# marquee_h.net
KiCad netlist of a schematic drawn in EAGLE
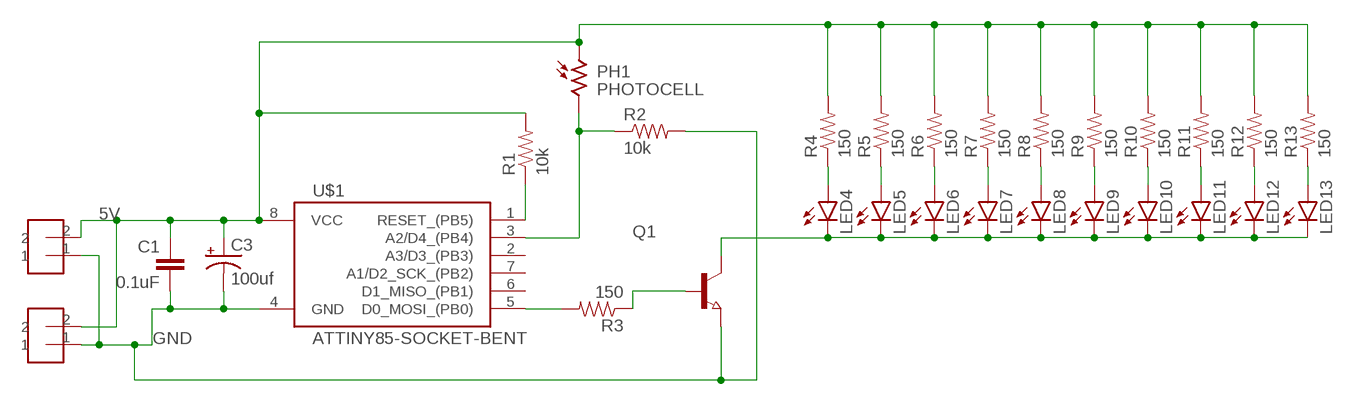
[diagram p0: schematic, sheet 1]

(export (version "E")
  (design (tool "Eeschema 10.0.6"))
  (components
    (comp (ref "C1")
      (value "0.1uF")
      (footprint "eagle-import:0805")
      (libsource (lib "eagle-import") (part "CAP-0805"))
    )
    (comp (ref "C3")
      (value "100uf")
      (footprint "eagle-import:PANASONIC_D")
      (libsource (lib "eagle-import") (part "CAP_POLD"))
    )
    (comp (ref "LED4")
      (value "LED0603")
      (footprint "eagle-import:LED-0603")
      (libsource (lib "eagle-import") (part "LED0603"))
    )
    (comp (ref "LED5")
      (value "LED0603")
      (footprint "eagle-import:LED-0603")
      (libsource (lib "eagle-import") (part "LED0603"))
    )
    (comp (ref "LED6")
      (value "LED0603")
      (footprint "eagle-import:LED-0603")
      (libsource (lib "eagle-import") (part "LED0603"))
    )
    (comp (ref "LED7")
      (value "LED0603")
      (footprint "eagle-import:LED-0603")
      (libsource (lib "eagle-import") (part "LED0603"))
    )
    (comp (ref "LED8")
      (value "LED0603")
      (footprint "eagle-import:LED-0603")
      (libsource (lib "eagle-import") (part "LED0603"))
    )
    (comp (ref "LED9")
      (value "LED0603")
      (footprint "eagle-import:LED-0603")
      (libsource (lib "eagle-import") (part "LED0603"))
    )
    (comp (ref "LED10")
      (value "LED0603")
      (footprint "eagle-import:LED-0603")
      (libsource (lib "eagle-import") (part "LED0603"))
    )
    (comp (ref "LED11")
      (value "LED0603")
      (footprint "eagle-import:LED-0603")
      (libsource (lib "eagle-import") (part "LED0603"))
    )
    (comp (ref "LED12")
      (value "LED0603")
      (footprint "eagle-import:LED-0603")
      (libsource (lib "eagle-import") (part "LED0603"))
    )
    (comp (ref "LED13")
      (value "LED0603")
      (footprint "eagle-import:LED-0603")
      (libsource (lib "eagle-import") (part "LED0603"))
    )
    (comp (ref "PH1")
      (value "PHOTOCELL")
      (footprint "eagle-import:PHOTOCELL_ADAFRUIT")
      (libsource (lib "eagle-import") (part "PHOTOCELL"))
    )
    (comp (ref "Q1")
      (value "TRANSISTOR-NPN-SOT23")
      (footprint "eagle-import:SOT23")
      (libsource (lib "eagle-import") (part "TRANSISTOR-NPN-SOT23"))
    )
    (comp (ref "R1")
      (value "10k")
      (footprint "eagle-import:0805")
      (libsource (lib "eagle-import") (part "RESISTOR-0805"))
    )
    (comp (ref "R2")
      (value "10k")
      (footprint "eagle-import:0805")
      (libsource (lib "eagle-import") (part "RESISTOR-0805"))
    )
    (comp (ref "R3")
      (value "150")
      (footprint "eagle-import:0805")
      (libsource (lib "eagle-import") (part "RESISTOR-0805"))
    )
    (comp (ref "R4")
      (value "150")
      (footprint "eagle-import:0603-RES")
      (libsource (lib "eagle-import") (part "RESISTOR0603"))
    )
    (comp (ref "R5")
      (value "150")
      (footprint "eagle-import:0603-RES")
      (libsource (lib "eagle-import") (part "RESISTOR0603"))
    )
    (comp (ref "R6")
      (value "150")
      (footprint "eagle-import:0603-RES")
      (libsource (lib "eagle-import") (part "RESISTOR0603"))
    )
    (comp (ref "R7")
      (value "150")
      (footprint "eagle-import:0603-RES")
      (libsource (lib "eagle-import") (part "RESISTOR0603"))
    )
    (comp (ref "R8")
      (value "150")
      (footprint "eagle-import:0603-RES")
      (libsource (lib "eagle-import") (part "RESISTOR0603"))
    )
    (comp (ref "R9")
      (value "150")
      (footprint "eagle-import:0603-RES")
      (libsource (lib "eagle-import") (part "RESISTOR0603"))
    )
    (comp (ref "R10")
      (value "150")
      (footprint "eagle-import:0603-RES")
      (libsource (lib "eagle-import") (part "RESISTOR0603"))
    )
    (comp (ref "R11")
      (value "150")
      (footprint "eagle-import:0603-RES")
      (libsource (lib "eagle-import") (part "RESISTOR0603"))
    )
    (comp (ref "R12")
      (value "150")
      (footprint "eagle-import:0603-RES")
      (libsource (lib "eagle-import") (part "RESISTOR0603"))
    )
    (comp (ref "R13")
      (value "150")
      (footprint "eagle-import:0603-RES")
      (libsource (lib "eagle-import") (part "RESISTOR0603"))
    )
    (comp (ref "U$1")
      (value "ATTINY85-SOCKET-BENT")
      (footprint "eagle-import:SOCKET-8PIN-BENT")
      (libsource (lib "eagle-import") (part "ATTINY85-SOCKET-BENT"))
    )
    (comp (ref "U$2")
      (value "HEADER-2")
      (footprint "eagle-import:HEADER-2")
      (libsource (lib "eagle-import") (part "HEADER-2"))
    )
    (comp (ref "U$3")
      (value "HEADER-2")
      (footprint "eagle-import:HEADER-2")
      (libsource (lib "eagle-import") (part "HEADER-2"))
    )
  )
  (nets
    (net (code "1") (name "/5V") (class "Default")
      (node (ref "C1") (pin "1") (pinfunction "1_1") (pintype "passive"))
      (node (ref "C3") (pin "+") (pinfunction "+_+") (pintype "passive"))
      (node (ref "PH1") (pin "1") (pinfunction "1_1") (pintype "passive"))
      (node (ref "R1") (pin "2") (pinfunction "2_2") (pintype "passive"))
      (node (ref "R10") (pin "2") (pinfunction "2_2") (pintype "passive"))
      (node (ref "R11") (pin "2") (pinfunction "2_2") (pintype "passive"))
      (node (ref "R12") (pin "2") (pinfunction "2_2") (pintype "passive"))
      (node (ref "R13") (pin "2") (pinfunction "2_2") (pintype "passive"))
      (node (ref "R4") (pin "2") (pinfunction "2_2") (pintype "passive"))
      (node (ref "R5") (pin "2") (pinfunction "2_2") (pintype "passive"))
      (node (ref "R6") (pin "2") (pinfunction "2_2") (pintype "passive"))
      (node (ref "R7") (pin "2") (pinfunction "2_2") (pintype "passive"))
      (node (ref "R8") (pin "2") (pinfunction "2_2") (pintype "passive"))
      (node (ref "R9") (pin "2") (pinfunction "2_2") (pintype "passive"))
      (node (ref "U$1") (pin "8") (pinfunction "VCC_8") (pintype "power_in"))
      (node (ref "U$2") (pin "2") (pinfunction "2_2") (pintype "bidirectional"))
      (node (ref "U$3") (pin "2") (pinfunction "2_2") (pintype "bidirectional"))
    )
    (net (code "2") (name "/GND") (class "Default")
      (node (ref "C1") (pin "2") (pinfunction "2_2") (pintype "passive"))
      (node (ref "C3") (pin "-") (pinfunction "-_-") (pintype "passive"))
      (node (ref "Q1") (pin "2") (pinfunction "E_2") (pintype "passive"))
      (node (ref "R2") (pin "2") (pinfunction "2_2") (pintype "passive"))
      (node (ref "U$1") (pin "4") (pinfunction "GND_4") (pintype "power_in"))
      (node (ref "U$2") (pin "1") (pinfunction "1_1") (pintype "bidirectional"))
      (node (ref "U$3") (pin "1") (pinfunction "1_1") (pintype "bidirectional"))
    )
    (net (code "3") (name "Net-(LED4-PadA)") (class "Default")
      (node (ref "LED4") (pin "A") (pinfunction "A_A") (pintype "passive"))
      (node (ref "R4") (pin "1") (pinfunction "1_1") (pintype "passive"))
    )
    (net (code "4") (name "Net-(LED5-PadA)") (class "Default")
      (node (ref "LED5") (pin "A") (pinfunction "A_A") (pintype "passive"))
      (node (ref "R5") (pin "1") (pinfunction "1_1") (pintype "passive"))
    )
    (net (code "5") (name "Net-(LED6-PadA)") (class "Default")
      (node (ref "LED6") (pin "A") (pinfunction "A_A") (pintype "passive"))
      (node (ref "R6") (pin "1") (pinfunction "1_1") (pintype "passive"))
    )
    (net (code "6") (name "Net-(LED7-PadA)") (class "Default")
      (node (ref "LED7") (pin "A") (pinfunction "A_A") (pintype "passive"))
      (node (ref "R7") (pin "1") (pinfunction "1_1") (pintype "passive"))
    )
    (net (code "7") (name "Net-(LED8-PadA)") (class "Default")
      (node (ref "LED8") (pin "A") (pinfunction "A_A") (pintype "passive"))
      (node (ref "R8") (pin "1") (pinfunction "1_1") (pintype "passive"))
    )
    (net (code "8") (name "Net-(LED9-PadA)") (class "Default")
      (node (ref "LED9") (pin "A") (pinfunction "A_A") (pintype "passive"))
      (node (ref "R9") (pin "1") (pinfunction "1_1") (pintype "passive"))
    )
    (net (code "9") (name "Net-(LED10-PadA)") (class "Default")
      (node (ref "LED10") (pin "A") (pinfunction "A_A") (pintype "passive"))
      (node (ref "R10") (pin "1") (pinfunction "1_1") (pintype "passive"))
    )
    (net (code "10") (name "Net-(LED11-PadA)") (class "Default")
      (node (ref "LED11") (pin "A") (pinfunction "A_A") (pintype "passive"))
      (node (ref "R11") (pin "1") (pinfunction "1_1") (pintype "passive"))
    )
    (net (code "11") (name "Net-(LED12-PadA)") (class "Default")
      (node (ref "LED12") (pin "A") (pinfunction "A_A") (pintype "passive"))
      (node (ref "R12") (pin "1") (pinfunction "1_1") (pintype "passive"))
    )
    (net (code "12") (name "Net-(LED13-PadA)") (class "Default")
      (node (ref "LED13") (pin "A") (pinfunction "A_A") (pintype "passive"))
      (node (ref "R13") (pin "1") (pinfunction "1_1") (pintype "passive"))
    )
    (net (code "13") (name "Net-(Q1-B)") (class "Default")
      (node (ref "Q1") (pin "1") (pinfunction "B_1") (pintype "passive"))
      (node (ref "R3") (pin "1") (pinfunction "1_1") (pintype "passive"))
    )
    (net (code "14") (name "Net-(Q1-C)") (class "Default")
      (node (ref "LED10") (pin "C") (pinfunction "C_C") (pintype "passive"))
      (node (ref "LED11") (pin "C") (pinfunction "C_C") (pintype "passive"))
      (node (ref "LED12") (pin "C") (pinfunction "C_C") (pintype "passive"))
      (node (ref "LED13") (pin "C") (pinfunction "C_C") (pintype "passive"))
      (node (ref "LED4") (pin "C") (pinfunction "C_C") (pintype "passive"))
      (node (ref "LED5") (pin "C") (pinfunction "C_C") (pintype "passive"))
      (node (ref "LED6") (pin "C") (pinfunction "C_C") (pintype "passive"))
      (node (ref "LED7") (pin "C") (pinfunction "C_C") (pintype "passive"))
      (node (ref "LED8") (pin "C") (pinfunction "C_C") (pintype "passive"))
      (node (ref "LED9") (pin "C") (pinfunction "C_C") (pintype "passive"))
      (node (ref "Q1") (pin "3") (pinfunction "C_3") (pintype "passive"))
    )
    (net (code "15") (name "Net-(U$1-A2{slash}D4_(PB4))") (class "Default")
      (node (ref "PH1") (pin "2") (pinfunction "2_2") (pintype "passive"))
      (node (ref "R2") (pin "1") (pinfunction "1_1") (pintype "passive"))
      (node (ref "U$1") (pin "3") (pinfunction "A2/D4_(PB4)_3") (pintype "bidirectional"))
    )
    (net (code "16") (name "Net-(U$1-D0_MOSI_(PB0))") (class "Default")
      (node (ref "R3") (pin "2") (pinfunction "2_2") (pintype "passive"))
      (node (ref "U$1") (pin "5") (pinfunction "D0_MOSI_(PB0)_5") (pintype "bidirectional"))
    )
    (net (code "17") (name "Net-(U$1-RESET_(PB5))") (class "Default")
      (node (ref "R1") (pin "1") (pinfunction "1_1") (pintype "passive"))
      (node (ref "U$1") (pin "1") (pinfunction "RESET_(PB5)_1") (pintype "bidirectional"))
    )
    (net (code "18") (name "unconnected-(U$1-A1{slash}D2_SCK_(PB2)-Pad7)") (class "Default")
      (node (ref "U$1") (pin "7") (pinfunction "A1/D2_SCK_(PB2)_7") (pintype "bidirectional"))
    )
    (net (code "19") (name "unconnected-(U$1-A3{slash}D3_(PB3)-Pad2)") (class "Default")
      (node (ref "U$1") (pin "2") (pinfunction "A3/D3_(PB3)_2") (pintype "bidirectional"))
    )
    (net (code "20") (name "unconnected-(U$1-D1_MISO_(PB1)-Pad6)") (class "Default")
      (node (ref "U$1") (pin "6") (pinfunction "D1_MISO_(PB1)_6") (pintype "bidirectional"))
    )
  )
)
